# raspidolly.net
KiCad netlist of a schematic drawn in EAGLE
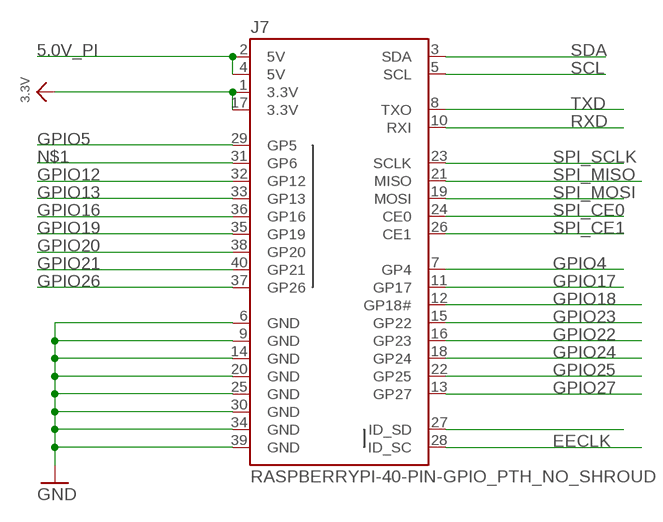
[diagram p0: schematic, sheet 1]
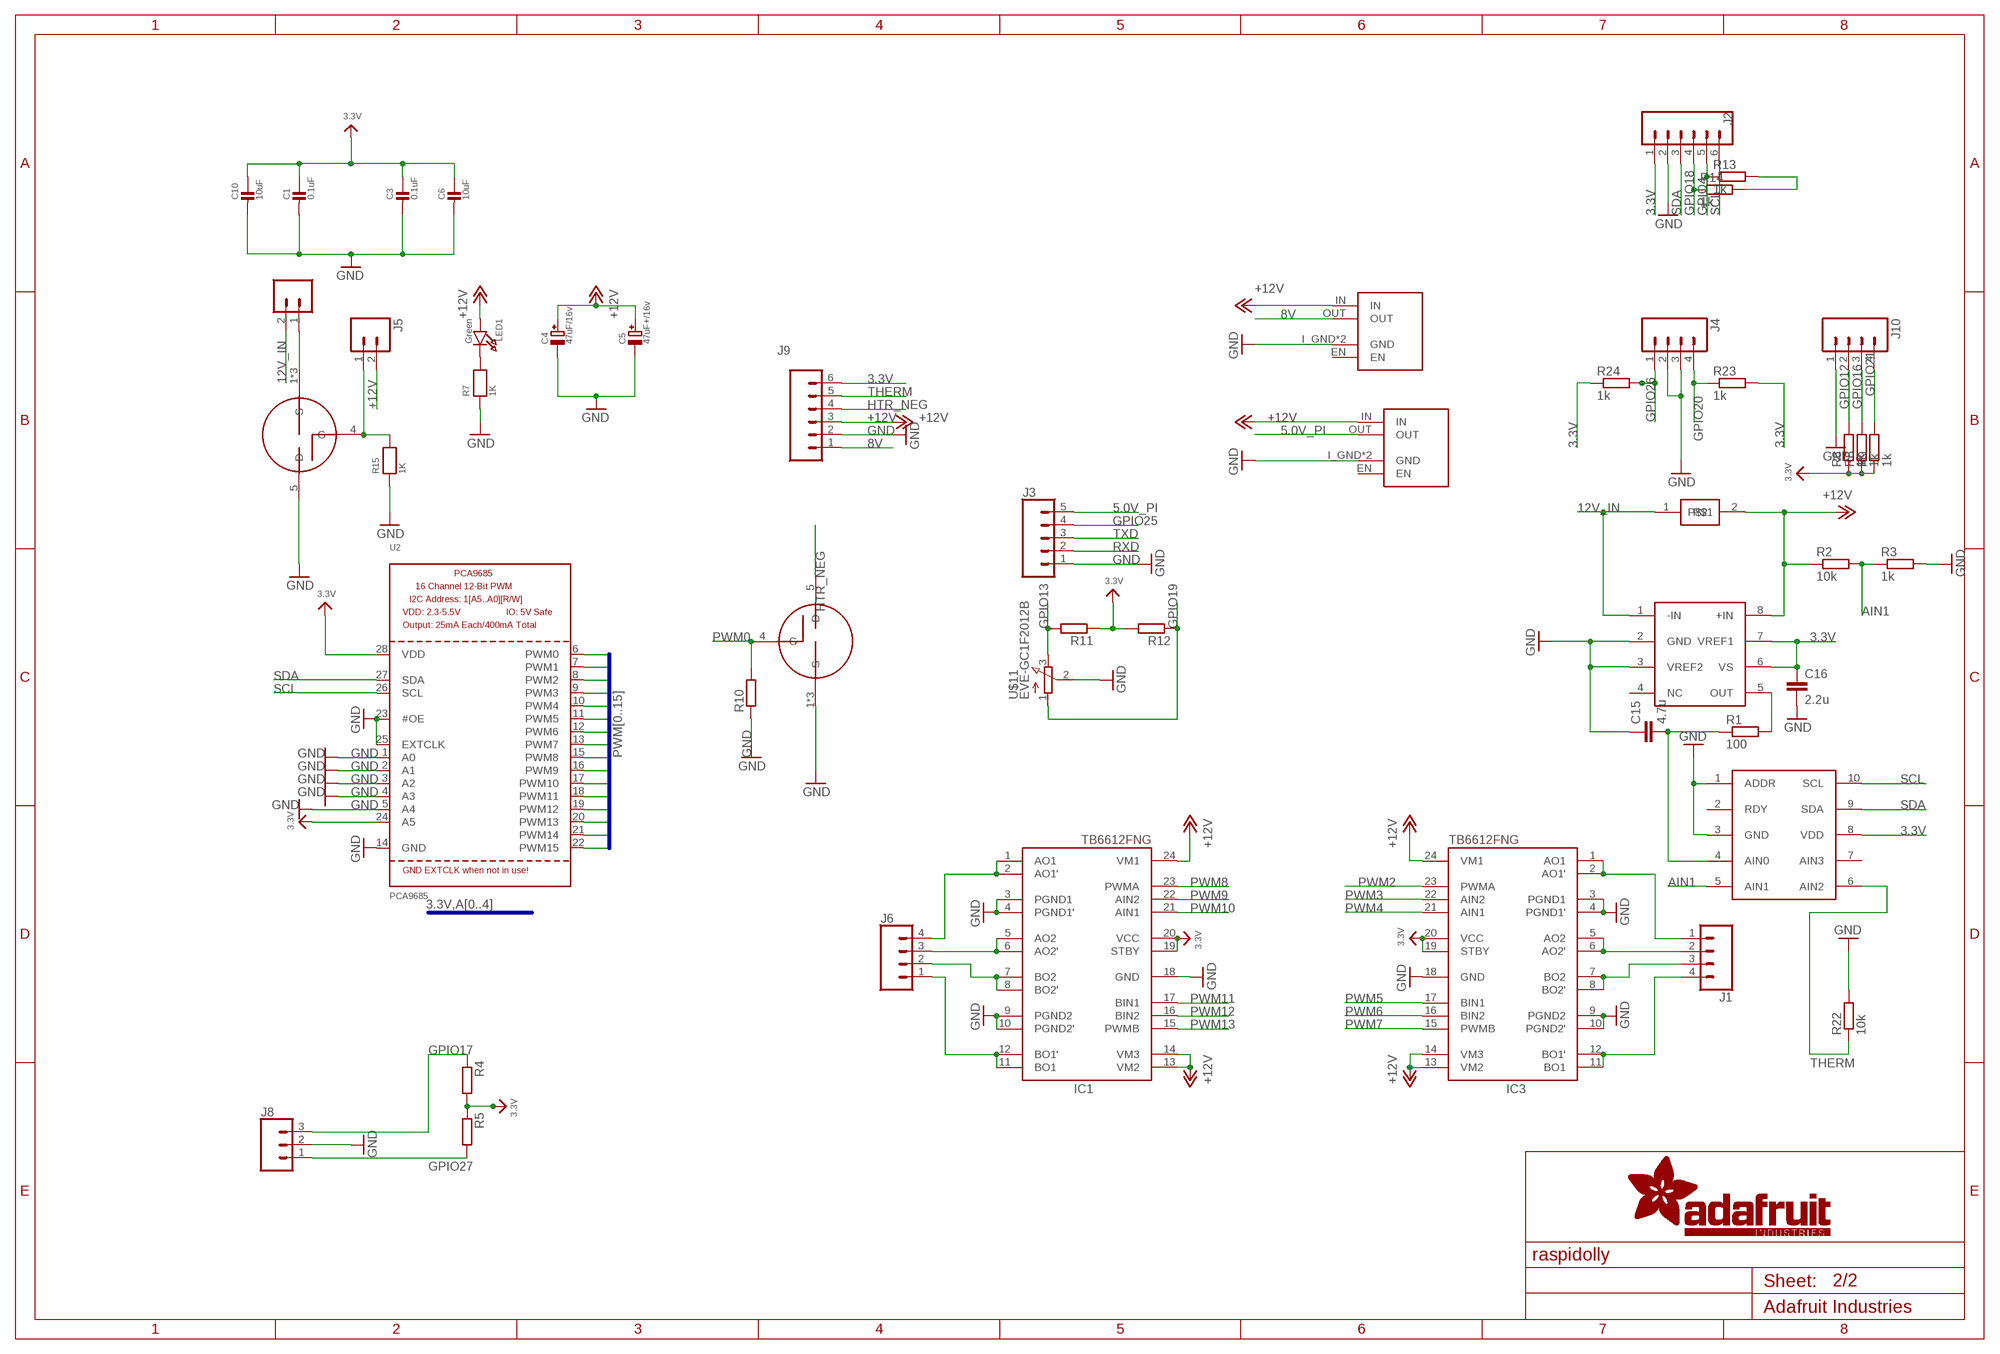
[diagram p1: schematic, sheet 2]

(export (version "E")
  (design (tool "Eeschema 10.0.6"))
  (components
    (comp (ref "C1")
      (value "0.1uF")
      (footprint "eagle-import:0805-NO")
      (libsource (lib "eagle-import") (part "CAP_CERAMIC0805-NOOUTLINE"))
    )
    (comp (ref "C3")
      (value "0.1uF")
      (footprint "eagle-import:0805-NO")
      (libsource (lib "eagle-import") (part "CAP_CERAMIC0805-NOOUTLINE"))
    )
    (comp (ref "C4")
      (value "47uF/16v")
      (footprint "eagle-import:PANASONIC_C")
      (libsource (lib "eagle-import") (part "CAP_ELECTROLYTICPANASONIC_C"))
    )
    (comp (ref "C5")
      (value "47uF+/16v")
      (footprint "eagle-import:PANASONIC_C")
      (libsource (lib "eagle-import") (part "CAP_ELECTROLYTICPANASONIC_C"))
    )
    (comp (ref "C6")
      (value "10uF")
      (footprint "eagle-import:0805-NO")
      (libsource (lib "eagle-import") (part "CAP_CERAMIC0805-NOOUTLINE"))
    )
    (comp (ref "C10")
      (value "10uF")
      (footprint "eagle-import:0805-NO")
      (libsource (lib "eagle-import") (part "CAP_CERAMIC0805-NOOUTLINE"))
    )
    (comp (ref "C15")
      (value "4.7u")
      (footprint "eagle-import:C0805")
      (libsource (lib "eagle-import") (part "C-EUC0805"))
    )
    (comp (ref "C16")
      (value "2.2u")
      (footprint "eagle-import:C0805")
      (libsource (lib "eagle-import") (part "C-EUC0805"))
    )
    (comp (ref "IC1")
      (value "TB6612FNG")
      (footprint "eagle-import:SSOP24")
      (libsource (lib "eagle-import") (part "TB6612FNG"))
    )
    (comp (ref "IC3")
      (value "TB6612FNG")
      (footprint "eagle-import:SSOP24")
      (libsource (lib "eagle-import") (part "TB6612FNG"))
    )
    (comp (ref "J1")
      (value "CONN_04")
      (footprint "eagle-import:1X04")
      (libsource (lib "eagle-import") (part "CONN_04"))
    )
    (comp (ref "J2")
      (value "CONN_061.27MM")
      (footprint "eagle-import:1X06_1.27MM")
      (libsource (lib "eagle-import") (part "CONN_061.27MM"))
    )
    (comp (ref "J3")
      (value "CONN_051.27MM")
      (footprint "eagle-import:1X05_1.27MM")
      (libsource (lib "eagle-import") (part "CONN_051.27MM"))
    )
    (comp (ref "J4")
      (value "M04JST")
      (footprint "eagle-import:1X04-1.5MM_JST")
      (libsource (lib "eagle-import") (part "M04JST"))
    )
    (comp (ref "J5")
      (value "M02PTH")
      (footprint "eagle-import:1X02")
      (libsource (lib "eagle-import") (part "M02PTH"))
    )
    (comp (ref "J6")
      (value "CONN_04")
      (footprint "eagle-import:1X04")
      (libsource (lib "eagle-import") (part "CONN_04"))
    )
    (comp (ref "J8")
      (value "CONN_03JST-PTH-VERT")
      (footprint "eagle-import:JST-3-PTH-VERT")
      (libsource (lib "eagle-import") (part "CONN_03JST-PTH-VERT"))
    )
    (comp (ref "J9")
      (value "CONN_061.27MM")
      (footprint "eagle-import:1X06_1.27MM")
      (libsource (lib "eagle-import") (part "CONN_061.27MM"))
    )
    (comp (ref "J10")
      (value "M04JST")
      (footprint "eagle-import:1X04-1.5MM_JST")
      (libsource (lib "eagle-import") (part "M04JST"))
    )
    (comp (ref "LED1")
      (value "Green")
      (footprint "eagle-import:CHIPLED_0805_NOOUTLINE")
      (libsource (lib "eagle-import") (part "LED0805_NOOUTLINE"))
    )
    (comp (ref "MPOWER")
      (value "CONN_02")
      (footprint "eagle-import:1X02")
      (libsource (lib "eagle-import") (part "CONN_02"))
    )
    (comp (ref "R1")
      (value "100")
      (footprint "eagle-import:R0805")
      (libsource (lib "eagle-import") (part "R-EU_R0805"))
    )
    (comp (ref "R2")
      (value "10k")
      (footprint "eagle-import:R0805")
      (libsource (lib "eagle-import") (part "R-EU_R0805"))
    )
    (comp (ref "R3")
      (value "1k")
      (footprint "eagle-import:R0805")
      (libsource (lib "eagle-import") (part "R-EU_R0805"))
    )
    (comp (ref "R4")
      (value "R-EU_R0805")
      (footprint "eagle-import:R0805")
      (libsource (lib "eagle-import") (part "resistor_R-EU_R0805"))
    )
    (comp (ref "R5")
      (value "R-EU_R0805")
      (footprint "eagle-import:R0805")
      (libsource (lib "eagle-import") (part "resistor_R-EU_R0805"))
    )
    (comp (ref "R6")
      (value "1k")
      (footprint "eagle-import:R0805")
      (libsource (lib "eagle-import") (part "R-EU_R0805"))
    )
    (comp (ref "R7")
      (value "1K")
      (footprint "eagle-import:0805-NO")
      (libsource (lib "eagle-import") (part "RESISTOR0805_NOOUTLINE"))
    )
    (comp (ref "R8")
      (value "1k")
      (footprint "eagle-import:R0805")
      (libsource (lib "eagle-import") (part "R-EU_R0805"))
    )
    (comp (ref "R9")
      (value "1k")
      (footprint "eagle-import:R0805")
      (libsource (lib "eagle-import") (part "R-EU_R0805"))
    )
    (comp (ref "R10")
      (value "R-EU_R0805")
      (footprint "eagle-import:R0805")
      (libsource (lib "eagle-import") (part "resistor_R-EU_R0805"))
    )
    (comp (ref "R11")
      (value "R-EU_R0805")
      (footprint "eagle-import:R0805")
      (libsource (lib "eagle-import") (part "resistor_R-EU_R0805"))
    )
    (comp (ref "R12")
      (value "R-EU_R0805")
      (footprint "eagle-import:R0805")
      (libsource (lib "eagle-import") (part "resistor_R-EU_R0805"))
    )
    (comp (ref "R13")
      (value "1k")
      (footprint "eagle-import:R0805")
      (libsource (lib "eagle-import") (part "R-EU_R0805"))
    )
    (comp (ref "R14")
      (value "1k")
      (footprint "eagle-import:R0805")
      (libsource (lib "eagle-import") (part "R-EU_R0805"))
    )
    (comp (ref "R15")
      (value "1K")
      (footprint "eagle-import:0805-NO")
      (libsource (lib "eagle-import") (part "RESISTOR0805_NOOUTLINE"))
    )
    (comp (ref "R22")
      (value "10k")
      (footprint "eagle-import:R0805")
      (libsource (lib "eagle-import") (part "R-EU_R0805"))
    )
    (comp (ref "R23")
      (value "1k")
      (footprint "eagle-import:R0805")
      (libsource (lib "eagle-import") (part "R-EU_R0805"))
    )
    (comp (ref "R24")
      (value "1k")
      (footprint "eagle-import:R0805")
      (libsource (lib "eagle-import") (part "R-EU_R0805"))
    )
    (comp (ref "U$5")
      (value "BUK9M")
      (footprint "eagle-import:LFPAK33")
      (libsource (lib "eagle-import") (part "BUK9M"))
    )
    (comp (ref "U$6")
      (value "BUK9M")
      (footprint "eagle-import:LFPAK33")
      (libsource (lib "eagle-import") (part "BUK9M"))
    )
    (comp (ref "U$8")
      (value "UFH-BUCK")
      (footprint "eagle-import:UFH-BUCK")
      (libsource (lib "eagle-import") (part "UFH-BUCK"))
    )
    (comp (ref "U$10")
      (value "UFH-BUCK")
      (footprint "eagle-import:UFH-BUCK")
      (libsource (lib "eagle-import") (part "UFH-BUCK"))
    )
    (comp (ref "U$11")
      (value "EVE-GC1F2012B")
      (footprint "eagle-import:EVE")
      (libsource (lib "eagle-import") (part "EVE-GC1F2012B"))
    )
    (comp (ref "U$14")
      (value "AD8418")
      (footprint "eagle-import:MSOP08")
      (libsource (lib "eagle-import") (part "AD8418"))
    )
    (comp (ref "U$15")
      (value "ADS1015")
      (footprint "eagle-import:VSSOP10")
      (libsource (lib "eagle-import") (part "ADS1015"))
    )
    (comp (ref "U$17")
      (value "RESISTOR")
      (footprint "eagle-import:3921")
      (libsource (lib "eagle-import") (part "RESISTOR"))
    )
    (comp (ref "U2")
      (value "PCA9685")
      (footprint "eagle-import:TSSOP28")
      (libsource (lib "eagle-import") (part "PCA9685"))
    )
    (comp (ref "J7")
      (value "RASPBERRYPI-40-PIN-GPIO_PTH_NO_SHROUD")
      (footprint "eagle-import:2X20")
      (libsource (lib "eagle-import") (part "RASPBERRYPI-40-PIN-GPIO_PTH_NO_SHROUD"))
    )
  )
  (nets
    (net (code "9") (name "+12V") (class "Default")
      (node (ref "C4") (pin "+") (pinfunction "+_+") (pintype "passive"))
      (node (ref "C5") (pin "+") (pinfunction "+_+") (pintype "passive"))
      (node (ref "IC1") (pin "13") (pinfunction "VM2_13") (pintype "power_in"))
      (node (ref "IC1") (pin "14") (pinfunction "VM3_14") (pintype "power_in"))
      (node (ref "IC1") (pin "24") (pinfunction "VM1_24") (pintype "power_in"))
      (node (ref "IC3") (pin "13") (pinfunction "VM2_13") (pintype "power_in"))
      (node (ref "IC3") (pin "14") (pinfunction "VM3_14") (pintype "power_in"))
      (node (ref "IC3") (pin "24") (pinfunction "VM1_24") (pintype "power_in"))
      (node (ref "J5") (pin "2") (pinfunction "2_2") (pintype "passive"))
      (node (ref "J9") (pin "3") (pinfunction "3_3") (pintype "passive"))
      (node (ref "LED1") (pin "A") (pinfunction "A_A") (pintype "passive"))
      (node (ref "R2") (pin "1") (pinfunction "1_1") (pintype "passive"))
      (node (ref "U$10") (pin "IN") (pinfunction "IN_IN") (pintype "bidirectional"))
      (node (ref "U$14") (pin "8") (pinfunction "+IN_8") (pintype "bidirectional"))
      (node (ref "U$17") (pin "2") (pinfunction "P$2_2") (pintype "bidirectional"))
      (node (ref "U$8") (pin "IN") (pinfunction "IN_IN") (pintype "bidirectional"))
    )
    (net (code "12") (name "3.3V") (class "Default")
      (node (ref "C1") (pin "1") (pinfunction "1_1") (pintype "passive"))
      (node (ref "C10") (pin "1") (pinfunction "1_1") (pintype "passive"))
      (node (ref "C16") (pin "1") (pinfunction "1_1") (pintype "passive"))
      (node (ref "C3") (pin "1") (pinfunction "1_1") (pintype "passive"))
      (node (ref "C6") (pin "1") (pinfunction "1_1") (pintype "passive"))
      (node (ref "IC1") (pin "19") (pinfunction "STBY_19") (pintype "input"))
      (node (ref "IC1") (pin "20") (pinfunction "VCC_20") (pintype "power_in"))
      (node (ref "IC3") (pin "19") (pinfunction "STBY_19") (pintype "input"))
      (node (ref "IC3") (pin "20") (pinfunction "VCC_20") (pintype "power_in"))
      (node (ref "J2") (pin "1") (pinfunction "1_1") (pintype "passive"))
      (node (ref "J7") (pin "1") (pinfunction "3.3V_1") (pintype "power_in"))
      (node (ref "J7") (pin "17") (pinfunction "3.3V_17") (pintype "power_in"))
      (node (ref "J9") (pin "6") (pinfunction "6_6") (pintype "passive"))
      (node (ref "R11") (pin "1") (pinfunction "1_1") (pintype "passive"))
      (node (ref "R12") (pin "2") (pinfunction "2_2") (pintype "passive"))
      (node (ref "R13") (pin "2") (pinfunction "2_2") (pintype "passive"))
      (node (ref "R14") (pin "2") (pinfunction "2_2") (pintype "passive"))
      (node (ref "R23") (pin "2") (pinfunction "2_2") (pintype "passive"))
      (node (ref "R24") (pin "1") (pinfunction "1_1") (pintype "passive"))
      (node (ref "R4") (pin "2") (pinfunction "2_2") (pintype "passive"))
      (node (ref "R5") (pin "1") (pinfunction "1_1") (pintype "passive"))
      (node (ref "R6") (pin "1") (pinfunction "1_1") (pintype "passive"))
      (node (ref "R8") (pin "1") (pinfunction "1_1") (pintype "passive"))
      (node (ref "R9") (pin "1") (pinfunction "1_1") (pintype "passive"))
      (node (ref "U$14") (pin "6") (pinfunction "VS_6") (pintype "bidirectional"))
      (node (ref "U$14") (pin "7") (pinfunction "VREF1_7") (pintype "bidirectional"))
      (node (ref "U$15") (pin "8") (pinfunction "VDD_8") (pintype "bidirectional"))
      (node (ref "U2") (pin "24") (pinfunction "A5_24") (pintype "bidirectional"))
      (node (ref "U2") (pin "28") (pinfunction "VDD_28") (pintype "power_in"))
    )
    (net (code "13") (name "5.0V_PI") (class "Default")
      (node (ref "J3") (pin "5") (pinfunction "5_5") (pintype "passive"))
      (node (ref "J7") (pin "2") (pinfunction "5V_2") (pintype "power_in"))
      (node (ref "J7") (pin "4") (pinfunction "5V_4") (pintype "power_in"))
      (node (ref "U$10") (pin "OUT") (pinfunction "OUT_OUT") (pintype "bidirectional"))
    )
    (net (code "14") (name "8V") (class "Default")
      (node (ref "J9") (pin "1") (pinfunction "1_1") (pintype "passive"))
      (node (ref "U$8") (pin "OUT") (pinfunction "OUT_OUT") (pintype "bidirectional"))
    )
    (net (code "15") (name "12V_IN") (class "Default")
      (node (ref "MPOWER") (pin "2") (pinfunction "2_2") (pintype "passive"))
      (node (ref "U$14") (pin "1") (pinfunction "-IN_1") (pintype "bidirectional"))
      (node (ref "U$17") (pin "1") (pinfunction "P$1_1") (pintype "bidirectional"))
    )
    (net (code "16") (name "AIN1") (class "Default")
      (node (ref "R2") (pin "2") (pinfunction "2_2") (pintype "passive"))
      (node (ref "R3") (pin "1") (pinfunction "1_1") (pintype "passive"))
      (node (ref "U$15") (pin "5") (pinfunction "AIN1_5") (pintype "bidirectional"))
    )
    (net (code "17") (name "EECLK") (class "Default")
      (node (ref "J7") (pin "28") (pinfunction "ID_SC_28") (pintype "bidirectional"))
    )
    (net (code "18") (name "GND") (class "Default")
      (node (ref "C1") (pin "2") (pinfunction "2_2") (pintype "passive"))
      (node (ref "C10") (pin "2") (pinfunction "2_2") (pintype "passive"))
      (node (ref "C15") (pin "1") (pinfunction "1_1") (pintype "passive"))
      (node (ref "C16") (pin "2") (pinfunction "2_2") (pintype "passive"))
      (node (ref "C3") (pin "2") (pinfunction "2_2") (pintype "passive"))
      (node (ref "C4") (pin "-") (pinfunction "-_-") (pintype "passive"))
      (node (ref "C5") (pin "-") (pinfunction "-_-") (pintype "passive"))
      (node (ref "C6") (pin "2") (pinfunction "2_2") (pintype "passive"))
      (node (ref "IC1") (pin "10") (pinfunction "PGND2'_10") (pintype "power_in"))
      (node (ref "IC1") (pin "18") (pinfunction "GND_18") (pintype "power_in"))
      (node (ref "IC1") (pin "3") (pinfunction "PGND1_3") (pintype "power_in"))
      (node (ref "IC1") (pin "4") (pinfunction "PGND1'_4") (pintype "power_in"))
      (node (ref "IC1") (pin "9") (pinfunction "PGND2_9") (pintype "power_in"))
      (node (ref "IC3") (pin "10") (pinfunction "PGND2'_10") (pintype "power_in"))
      (node (ref "IC3") (pin "18") (pinfunction "GND_18") (pintype "power_in"))
      (node (ref "IC3") (pin "3") (pinfunction "PGND1_3") (pintype "power_in"))
      (node (ref "IC3") (pin "4") (pinfunction "PGND1'_4") (pintype "power_in"))
      (node (ref "IC3") (pin "9") (pinfunction "PGND2_9") (pintype "power_in"))
      (node (ref "J10") (pin "1") (pinfunction "1_1") (pintype "passive"))
      (node (ref "J2") (pin "2") (pinfunction "2_2") (pintype "passive"))
      (node (ref "J3") (pin "1") (pinfunction "1_1") (pintype "passive"))
      (node (ref "J4") (pin "2") (pinfunction "2_2") (pintype "passive"))
      (node (ref "J4") (pin "3") (pinfunction "3_3") (pintype "passive"))
      (node (ref "J7") (pin "14") (pinfunction "GND_14") (pintype "power_in"))
      (node (ref "J7") (pin "20") (pinfunction "GND_20") (pintype "power_in"))
      (node (ref "J7") (pin "25") (pinfunction "GND_25") (pintype "power_in"))
      (node (ref "J7") (pin "30") (pinfunction "GND_30") (pintype "power_in"))
      (node (ref "J7") (pin "34") (pinfunction "GND_34") (pintype "power_in"))
      (node (ref "J7") (pin "39") (pinfunction "GND_39") (pintype "power_in"))
      (node (ref "J7") (pin "6") (pinfunction "GND_6") (pintype "power_in"))
      (node (ref "J7") (pin "9") (pinfunction "GND_9") (pintype "power_in"))
      (node (ref "J8") (pin "2") (pinfunction "2_2") (pintype "passive"))
      (node (ref "J9") (pin "2") (pinfunction "2_2") (pintype "passive"))
      (node (ref "R10") (pin "1") (pinfunction "1_1") (pintype "passive"))
      (node (ref "R15") (pin "1") (pinfunction "1_1") (pintype "passive"))
      (node (ref "R22") (pin "2") (pinfunction "2_2") (pintype "passive"))
      (node (ref "R3") (pin "2") (pinfunction "2_2") (pintype "passive"))
      (node (ref "R7") (pin "1") (pinfunction "1_1") (pintype "passive"))
      (node (ref "U$10") (pin "I_GND") (pinfunction "GND_I_GND") (pintype "bidirectional"))
      (node (ref "U$10") (pin "O_GND") (pinfunction "GND_O_GND") (pintype "bidirectional"))
      (node (ref "U$11") (pin "2") (pinfunction "COM_2") (pintype "passive"))
      (node (ref "U$14") (pin "2") (pinfunction "GND_2") (pintype "bidirectional"))
      (node (ref "U$14") (pin "3") (pinfunction "VREF2_3") (pintype "bidirectional"))
      (node (ref "U$15") (pin "1") (pinfunction "ADDR_1") (pintype "bidirectional"))
      (node (ref "U$15") (pin "3") (pinfunction "GND_3") (pintype "bidirectional"))
      (node (ref "U$5") (pin "1") (pinfunction "S_1") (pintype "bidirectional"))
      (node (ref "U$5") (pin "2") (pinfunction "S_2") (pintype "bidirectional"))
      (node (ref "U$5") (pin "3") (pinfunction "S_3") (pintype "bidirectional"))
      (node (ref "U$6") (pin "5") (pinfunction "D_5") (pintype "bidirectional"))
      (node (ref "U$8") (pin "I_GND") (pinfunction "GND_I_GND") (pintype "bidirectional"))
      (node (ref "U$8") (pin "O_GND") (pinfunction "GND_O_GND") (pintype "bidirectional"))
      (node (ref "U2") (pin "1") (pinfunction "A0_1") (pintype "bidirectional"))
      (node (ref "U2") (pin "14") (pinfunction "GND_14") (pintype "power_in"))
      (node (ref "U2") (pin "2") (pinfunction "A1_2") (pintype "bidirectional"))
      (node (ref "U2") (pin "23") (pinfunction "#OE_23") (pintype "input"))
      (node (ref "U2") (pin "25") (pinfunction "EXTCLK_25") (pintype "input"))
      (node (ref "U2") (pin "3") (pinfunction "A2_3") (pintype "bidirectional"))
      (node (ref "U2") (pin "4") (pinfunction "A3_4") (pintype "bidirectional"))
      (node (ref "U2") (pin "5") (pinfunction "A4_5") (pintype "bidirectional"))
    )
    (net (code "19") (name "GPIO4") (class "Default")
      (node (ref "J2") (pin "5") (pinfunction "5_5") (pintype "passive"))
      (node (ref "J7") (pin "7") (pinfunction "GP4_7") (pintype "bidirectional"))
      (node (ref "R13") (pin "1") (pinfunction "1_1") (pintype "passive"))
    )
    (net (code "20") (name "GPIO5") (class "Default")
      (node (ref "J7") (pin "29") (pinfunction "GP5_29") (pintype "bidirectional"))
    )
    (net (code "21") (name "GPIO12") (class "Default")
      (node (ref "J10") (pin "2") (pinfunction "2_2") (pintype "passive"))
      (node (ref "J7") (pin "32") (pinfunction "GP12_32") (pintype "bidirectional"))
      (node (ref "R6") (pin "2") (pinfunction "2_2") (pintype "passive"))
    )
    (net (code "22") (name "GPIO13") (class "Default")
      (node (ref "J7") (pin "33") (pinfunction "GP13_33") (pintype "bidirectional"))
      (node (ref "R11") (pin "2") (pinfunction "2_2") (pintype "passive"))
      (node (ref "U$11") (pin "3") (pinfunction "B_3") (pintype "passive"))
    )
    (net (code "23") (name "GPIO16") (class "Default")
      (node (ref "J10") (pin "3") (pinfunction "3_3") (pintype "passive"))
      (node (ref "J7") (pin "36") (pinfunction "GP16_36") (pintype "bidirectional"))
      (node (ref "R8") (pin "2") (pinfunction "2_2") (pintype "passive"))
    )
    (net (code "24") (name "GPIO17") (class "Default")
      (node (ref "J7") (pin "11") (pinfunction "GP17_11") (pintype "bidirectional"))
      (node (ref "J8") (pin "3") (pinfunction "3_3") (pintype "passive"))
      (node (ref "R4") (pin "1") (pinfunction "1_1") (pintype "passive"))
    )
    (net (code "25") (name "GPIO18") (class "Default")
      (node (ref "J2") (pin "4") (pinfunction "4_4") (pintype "passive"))
      (node (ref "J7") (pin "12") (pinfunction "GP18#_12") (pintype "bidirectional"))
      (node (ref "R14") (pin "1") (pinfunction "1_1") (pintype "passive"))
    )
    (net (code "26") (name "GPIO19") (class "Default")
      (node (ref "J7") (pin "35") (pinfunction "GP19_35") (pintype "bidirectional"))
      (node (ref "R12") (pin "1") (pinfunction "1_1") (pintype "passive"))
      (node (ref "U$11") (pin "1") (pinfunction "A_1") (pintype "passive"))
    )
    (net (code "27") (name "GPIO20") (class "Default")
      (node (ref "J4") (pin "4") (pinfunction "4_4") (pintype "passive"))
      (node (ref "J7") (pin "38") (pinfunction "GP20_38") (pintype "bidirectional"))
      (node (ref "R23") (pin "1") (pinfunction "1_1") (pintype "passive"))
    )
    (net (code "28") (name "GPIO21") (class "Default")
      (node (ref "J10") (pin "4") (pinfunction "4_4") (pintype "passive"))
      (node (ref "J7") (pin "40") (pinfunction "GP21_40") (pintype "bidirectional"))
      (node (ref "R9") (pin "2") (pinfunction "2_2") (pintype "passive"))
    )
    (net (code "29") (name "GPIO22") (class "Default")
      (node (ref "J7") (pin "15") (pinfunction "GP22_15") (pintype "bidirectional"))
    )
    (net (code "30") (name "GPIO23") (class "Default")
      (node (ref "J7") (pin "16") (pinfunction "GP23_16") (pintype "bidirectional"))
    )
    (net (code "31") (name "GPIO24") (class "Default")
      (node (ref "J7") (pin "18") (pinfunction "GP24_18") (pintype "bidirectional"))
    )
    (net (code "32") (name "GPIO25") (class "Default")
      (node (ref "J3") (pin "4") (pinfunction "4_4") (pintype "passive"))
      (node (ref "J7") (pin "22") (pinfunction "GP25_22") (pintype "bidirectional"))
    )
    (net (code "33") (name "GPIO26") (class "Default")
      (node (ref "J4") (pin "1") (pinfunction "1_1") (pintype "passive"))
      (node (ref "J7") (pin "37") (pinfunction "GP26_37") (pintype "bidirectional"))
      (node (ref "R24") (pin "2") (pinfunction "2_2") (pintype "passive"))
    )
    (net (code "34") (name "GPIO27") (class "Default")
      (node (ref "J7") (pin "13") (pinfunction "GP27_13") (pintype "bidirectional"))
      (node (ref "J8") (pin "1") (pinfunction "1_1") (pintype "passive"))
      (node (ref "R5") (pin "2") (pinfunction "2_2") (pintype "passive"))
    )
    (net (code "35") (name "HTR_NEG") (class "Default")
      (node (ref "J9") (pin "4") (pinfunction "4_4") (pintype "passive"))
      (node (ref "U$5") (pin "5") (pinfunction "D_5") (pintype "bidirectional"))
    )
    (net (code "36") (name "N$1") (class "Default")
      (node (ref "J7") (pin "31") (pinfunction "GP6_31") (pintype "bidirectional"))
    )
    (net (code "37") (name "Net-(IC1-AO1')") (class "Default")
      (node (ref "IC1") (pin "1") (pinfunction "AO1_1") (pintype "output"))
      (node (ref "IC1") (pin "2") (pinfunction "AO1'_2") (pintype "output"))
      (node (ref "J6") (pin "4") (pinfunction "4_4") (pintype "passive"))
    )
    (net (code "38") (name "Net-(IC1-AO2')") (class "Default")
      (node (ref "IC1") (pin "5") (pinfunction "AO2_5") (pintype "output"))
      (node (ref "IC1") (pin "6") (pinfunction "AO2'_6") (pintype "output"))
      (node (ref "J6") (pin "3") (pinfunction "3_3") (pintype "passive"))
    )
    (net (code "39") (name "Net-(IC1-BO1')") (class "Default")
      (node (ref "IC1") (pin "11") (pinfunction "BO1_11") (pintype "output"))
      (node (ref "IC1") (pin "12") (pinfunction "BO1'_12") (pintype "output"))
      (node (ref "J6") (pin "1") (pinfunction "1_1") (pintype "passive"))
    )
    (net (code "40") (name "Net-(IC1-BO2')") (class "Default")
      (node (ref "IC1") (pin "7") (pinfunction "BO2_7") (pintype "output"))
      (node (ref "IC1") (pin "8") (pinfunction "BO2'_8") (pintype "output"))
      (node (ref "J6") (pin "2") (pinfunction "2_2") (pintype "passive"))
    )
    (net (code "41") (name "Net-(IC3-AO1')") (class "Default")
      (node (ref "IC3") (pin "1") (pinfunction "AO1_1") (pintype "output"))
      (node (ref "IC3") (pin "2") (pinfunction "AO1'_2") (pintype "output"))
      (node (ref "J1") (pin "1") (pinfunction "1_1") (pintype "passive"))
    )
    (net (code "42") (name "Net-(IC3-AO2')") (class "Default")
      (node (ref "IC3") (pin "5") (pinfunction "AO2_5") (pintype "output"))
      (node (ref "IC3") (pin "6") (pinfunction "AO2'_6") (pintype "output"))
      (node (ref "J1") (pin "2") (pinfunction "2_2") (pintype "passive"))
    )
    (net (code "43") (name "Net-(IC3-BO1')") (class "Default")
      (node (ref "IC3") (pin "11") (pinfunction "BO1_11") (pintype "output"))
      (node (ref "IC3") (pin "12") (pinfunction "BO1'_12") (pintype "output"))
      (node (ref "J1") (pin "4") (pinfunction "4_4") (pintype "passive"))
    )
    (net (code "44") (name "Net-(IC3-BO2')") (class "Default")
      (node (ref "IC3") (pin "7") (pinfunction "BO2_7") (pintype "output"))
      (node (ref "IC3") (pin "8") (pinfunction "BO2'_8") (pintype "output"))
      (node (ref "J1") (pin "3") (pinfunction "3_3") (pintype "passive"))
    )
    (net (code "45") (name "Net-(LED1-PadC)") (class "Default")
      (node (ref "LED1") (pin "C") (pinfunction "C_C") (pintype "passive"))
      (node (ref "R7") (pin "2") (pinfunction "2_2") (pintype "passive"))
    )
    (net (code "46") (name "Net-(MPOWER-Pad1)") (class "Default")
      (node (ref "MPOWER") (pin "1") (pinfunction "1_1") (pintype "passive"))
      (node (ref "U$6") (pin "1") (pinfunction "S_1") (pintype "bidirectional"))
      (node (ref "U$6") (pin "2") (pinfunction "S_2") (pintype "bidirectional"))
      (node (ref "U$6") (pin "3") (pinfunction "S_3") (pintype "bidirectional"))
    )
    (net (code "47") (name "Net-(U$6-G)") (class "Default")
      (node (ref "J5") (pin "1") (pinfunction "1_1") (pintype "passive"))
      (node (ref "R15") (pin "2") (pinfunction "2_2") (pintype "passive"))
      (node (ref "U$6") (pin "4") (pinfunction "G_4") (pintype "bidirectional"))
    )
    (net (code "48") (name "Net-(U$14-OUT)") (class "Default")
      (node (ref "R1") (pin "2") (pinfunction "2_2") (pintype "passive"))
      (node (ref "U$14") (pin "5") (pinfunction "OUT_5") (pintype "bidirectional"))
    )
    (net (code "49") (name "Net-(U$15-AIN0)") (class "Default")
      (node (ref "C15") (pin "2") (pinfunction "2_2") (pintype "passive"))
      (node (ref "R1") (pin "1") (pinfunction "1_1") (pintype "passive"))
      (node (ref "U$15") (pin "4") (pinfunction "AIN0_4") (pintype "bidirectional"))
    )
    (net (code "50") (name "PWM0") (class "Default")
      (node (ref "R10") (pin "2") (pinfunction "2_2") (pintype "passive"))
      (node (ref "U$5") (pin "4") (pinfunction "G_4") (pintype "bidirectional"))
      (node (ref "U2") (pin "6") (pinfunction "PWM0_6") (pintype "output"))
    )
    (net (code "51") (name "PWM2") (class "Default")
      (node (ref "IC3") (pin "23") (pinfunction "PWMA_23") (pintype "input"))
      (node (ref "U2") (pin "8") (pinfunction "PWM2_8") (pintype "output"))
    )
    (net (code "52") (name "PWM3") (class "Default")
      (node (ref "IC3") (pin "22") (pinfunction "AIN2_22") (pintype "input"))
      (node (ref "U2") (pin "9") (pinfunction "PWM3_9") (pintype "output"))
    )
    (net (code "53") (name "PWM4") (class "Default")
      (node (ref "IC3") (pin "21") (pinfunction "AIN1_21") (pintype "input"))
      (node (ref "U2") (pin "10") (pinfunction "PWM4_10") (pintype "output"))
    )
    (net (code "54") (name "PWM5") (class "Default")
      (node (ref "IC3") (pin "17") (pinfunction "BIN1_17") (pintype "input"))
      (node (ref "U2") (pin "11") (pinfunction "PWM5_11") (pintype "output"))
    )
    (net (code "55") (name "PWM6") (class "Default")
      (node (ref "IC3") (pin "16") (pinfunction "BIN2_16") (pintype "input"))
      (node (ref "U2") (pin "12") (pinfunction "PWM6_12") (pintype "output"))
    )
    (net (code "56") (name "PWM7") (class "Default")
      (node (ref "IC3") (pin "15") (pinfunction "PWMB_15") (pintype "input"))
      (node (ref "U2") (pin "13") (pinfunction "PWM7_13") (pintype "output"))
    )
    (net (code "57") (name "PWM8") (class "Default")
      (node (ref "IC1") (pin "23") (pinfunction "PWMA_23") (pintype "input"))
      (node (ref "U2") (pin "15") (pinfunction "PWM8_15") (pintype "output"))
    )
    (net (code "58") (name "PWM9") (class "Default")
      (node (ref "IC1") (pin "22") (pinfunction "AIN2_22") (pintype "input"))
      (node (ref "U2") (pin "16") (pinfunction "PWM9_16") (pintype "output"))
    )
    (net (code "59") (name "PWM10") (class "Default")
      (node (ref "IC1") (pin "21") (pinfunction "AIN1_21") (pintype "input"))
      (node (ref "U2") (pin "17") (pinfunction "PWM10_17") (pintype "output"))
    )
    (net (code "60") (name "PWM11") (class "Default")
      (node (ref "IC1") (pin "17") (pinfunction "BIN1_17") (pintype "input"))
      (node (ref "U2") (pin "18") (pinfunction "PWM11_18") (pintype "output"))
    )
    (net (code "61") (name "PWM12") (class "Default")
      (node (ref "IC1") (pin "16") (pinfunction "BIN2_16") (pintype "input"))
      (node (ref "U2") (pin "19") (pinfunction "PWM12_19") (pintype "output"))
    )
    (net (code "62") (name "PWM13") (class "Default")
      (node (ref "IC1") (pin "15") (pinfunction "PWMB_15") (pintype "input"))
      (node (ref "U2") (pin "20") (pinfunction "PWM13_20") (pintype "output"))
    )
    (net (code "63") (name "RXD") (class "Default")
      (node (ref "J3") (pin "2") (pinfunction "2_2") (pintype "passive"))
      (node (ref "J7") (pin "10") (pinfunction "RXI_10") (pintype "input"))
    )
    (net (code "64") (name "SCL") (class "Default")
      (node (ref "J2") (pin "6") (pinfunction "6_6") (pintype "passive"))
      (node (ref "J7") (pin "5") (pinfunction "SCL_5") (pintype "bidirectional"))
      (node (ref "U$15") (pin "10") (pinfunction "SCL_10") (pintype "bidirectional"))
      (node (ref "U2") (pin "26") (pinfunction "SCL_26") (pintype "bidirectional"))
    )
    (net (code "65") (name "SDA") (class "Default")
      (node (ref "J2") (pin "3") (pinfunction "3_3") (pintype "passive"))
      (node (ref "J7") (pin "3") (pinfunction "SDA_3") (pintype "bidirectional"))
      (node (ref "U$15") (pin "9") (pinfunction "SDA_9") (pintype "bidirectional"))
      (node (ref "U2") (pin "27") (pinfunction "SDA_27") (pintype "bidirectional"))
    )
    (net (code "66") (name "SPI_CE0") (class "Default")
      (node (ref "J7") (pin "24") (pinfunction "CE0_24") (pintype "output"))
    )
    (net (code "67") (name "SPI_CE1") (class "Default")
      (node (ref "J7") (pin "26") (pinfunction "CE1_26") (pintype "output"))
    )
    (net (code "68") (name "SPI_MISO") (class "Default")
      (node (ref "J7") (pin "21") (pinfunction "MISO_21") (pintype "input"))
    )
    (net (code "69") (name "SPI_MOSI") (class "Default")
      (node (ref "J7") (pin "19") (pinfunction "MOSI_19") (pintype "output"))
    )
    (net (code "70") (name "SPI_SCLK") (class "Default")
      (node (ref "J7") (pin "23") (pinfunction "SCLK_23") (pintype "output"))
    )
    (net (code "71") (name "THERM") (class "Default")
      (node (ref "J9") (pin "5") (pinfunction "5_5") (pintype "passive"))
      (node (ref "R22") (pin "1") (pinfunction "1_1") (pintype "passive"))
      (node (ref "U$15") (pin "6") (pinfunction "AIN2_6") (pintype "bidirectional"))
    )
    (net (code "72") (name "TXD") (class "Default")
      (node (ref "J3") (pin "3") (pinfunction "3_3") (pintype "passive"))
      (node (ref "J7") (pin "8") (pinfunction "TXO_8") (pintype "output"))
    )
    (net (code "73") (name "unconnected-(J7-ID_SD-Pad27)") (class "Default")
      (node (ref "J7") (pin "27") (pinfunction "ID_SD_27") (pintype "bidirectional"))
    )
    (net (code "74") (name "unconnected-(U$8-PadEN)") (class "Default")
      (node (ref "U$8") (pin "EN") (pinfunction "EN_EN") (pintype "bidirectional"))
    )
    (net (code "75") (name "unconnected-(U$10-PadEN)") (class "Default")
      (node (ref "U$10") (pin "EN") (pinfunction "EN_EN") (pintype "bidirectional"))
    )
    (net (code "76") (name "unconnected-(U$14-NC-Pad4)") (class "Default")
      (node (ref "U$14") (pin "4") (pinfunction "NC_4") (pintype "bidirectional"))
    )
    (net (code "77") (name "unconnected-(U$15-AIN3-Pad7)") (class "Default")
      (node (ref "U$15") (pin "7") (pinfunction "AIN3_7") (pintype "bidirectional"))
    )
    (net (code "78") (name "unconnected-(U$15-RDY-Pad2)") (class "Default")
      (node (ref "U$15") (pin "2") (pinfunction "RDY_2") (pintype "bidirectional"))
    )
    (net (code "79") (name "unconnected-(U2-PWM1-Pad7)") (class "Default")
      (node (ref "U2") (pin "7") (pinfunction "PWM1_7") (pintype "output"))
    )
    (net (code "80") (name "unconnected-(U2-PWM14-Pad21)") (class "Default")
      (node (ref "U2") (pin "21") (pinfunction "PWM14_21") (pintype "output"))
    )
    (net (code "81") (name "unconnected-(U2-PWM15-Pad22)") (class "Default")
      (node (ref "U2") (pin "22") (pinfunction "PWM15_22") (pintype "output"))
    )
  )
)
